# usb-led.net
KiCad netlist of a schematic drawn in EAGLE
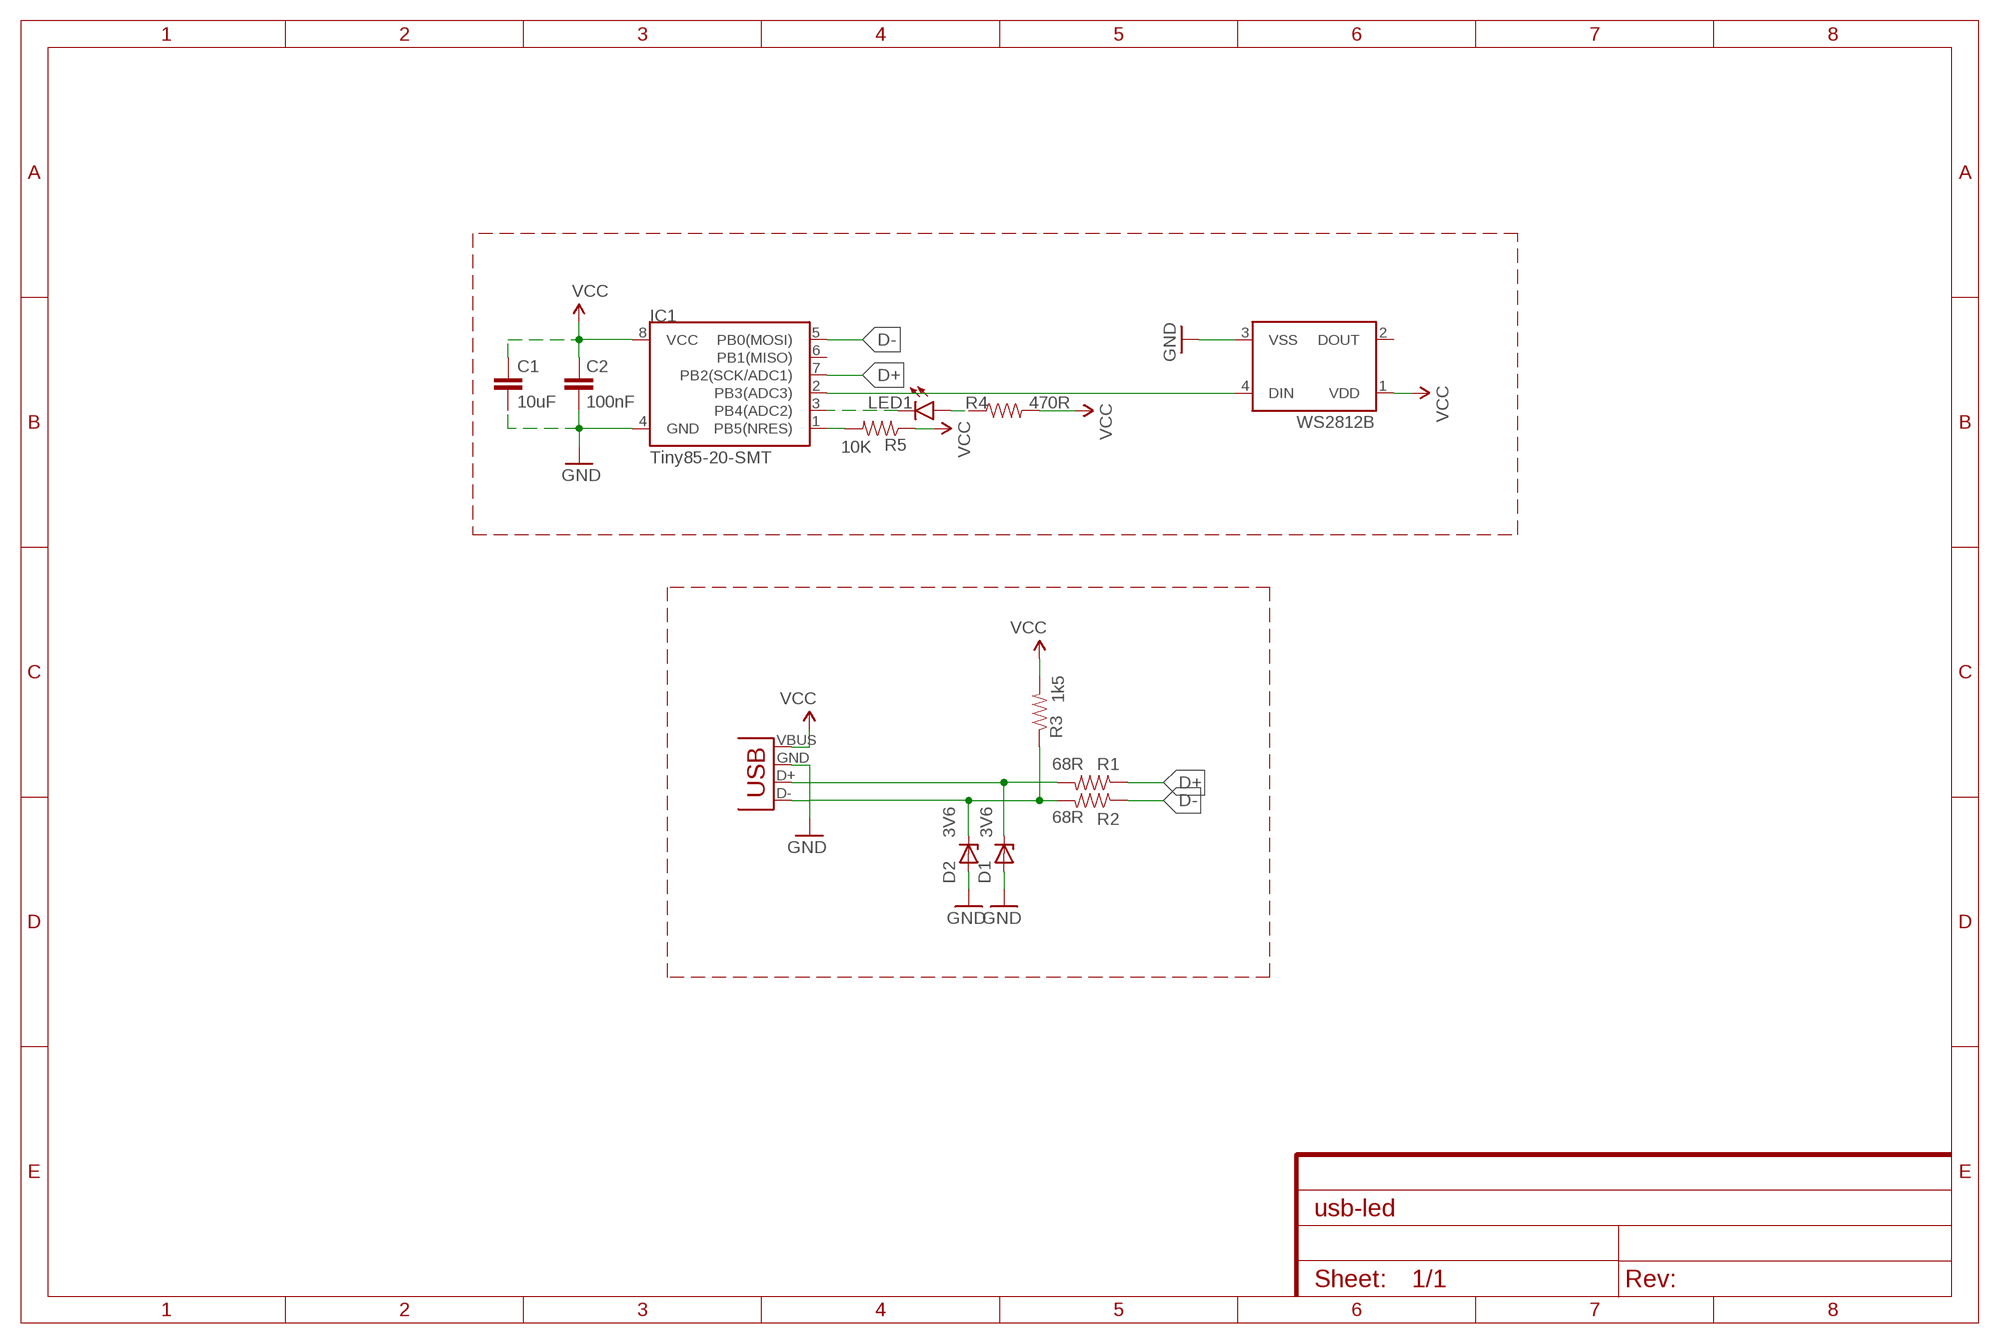
[diagram p0: schematic, sheet 1]

(export (version "E")
  (design (tool "Eeschema 10.0.6"))
  (components
    (comp (ref "C1")
      (value "10uF")
      (footprint "eagle-import:C0805")
      (libsource (lib "eagle-import") (part "C-EUC0805"))
    )
    (comp (ref "C2")
      (value "100nF")
      (footprint "eagle-import:0805")
      (libsource (lib "eagle-import") (part "CAP0805"))
    )
    (comp (ref "D1")
      (value "3V6")
      (footprint "eagle-import:ZD0603")
      (libsource (lib "eagle-import") (part "ZD0603"))
    )
    (comp (ref "D2")
      (value "3V6")
      (footprint "eagle-import:ZD0603")
      (libsource (lib "eagle-import") (part "ZD0603"))
    )
    (comp (ref "IC1")
      (value "Tiny85-20-SMT")
      (footprint "eagle-import:SO08-EIAJ")
      (libsource (lib "eagle-import") (part "ATTINY45TINY85-20-SMT"))
    )
    (comp (ref "LED1")
      (value "LED0603")
      (footprint "eagle-import:LED-0603")
      (libsource (lib "eagle-import") (part "LED0603"))
    )
    (comp (ref "R1")
      (value "68R")
      (footprint "eagle-import:0603-RES")
      (libsource (lib "eagle-import") (part "RESISTOR0603"))
    )
    (comp (ref "R2")
      (value "68R")
      (footprint "eagle-import:0603-RES")
      (libsource (lib "eagle-import") (part "RESISTOR0603"))
    )
    (comp (ref "R3")
      (value "1k5")
      (footprint "eagle-import:0603-RES")
      (libsource (lib "eagle-import") (part "RESISTOR0603"))
    )
    (comp (ref "R4")
      (value "470R")
      (footprint "eagle-import:0603-RES")
      (libsource (lib "eagle-import") (part "RESISTOR0603"))
    )
    (comp (ref "R5")
      (value "10K")
      (footprint "eagle-import:0603-RES")
      (libsource (lib "eagle-import") (part "RESISTOR0603-RES"))
    )
    (comp (ref "USB")
      (value "USB-A-H")
      (footprint "eagle-import:USB-A-H")
      (libsource (lib "eagle-import") (part "USB-A-H"))
    )
    (comp (ref "WS2812B")
      (value "WS2812B")
      (footprint "eagle-import:WS2812B")
      (libsource (lib "eagle-import") (part "WS2812B"))
    )
  )
  (nets
    (net (code "1") (name "/EXT_D-") (class "Default")
      (node (ref "D2") (pin "K") (pinfunction "C_K") (pintype "passive"))
      (node (ref "R2") (pin "2") (pinfunction "2_2") (pintype "passive"))
      (node (ref "R3") (pin "1") (pinfunction "1_1") (pintype "passive"))
      (node (ref "USB") (pin "D-") (pinfunction "D+_D-") (pintype "bidirectional"))
    )
    (net (code "2") (name "D+") (class "Default")
      (node (ref "IC1") (pin "7") (pinfunction "PB2(SCK/ADC1)_7") (pintype "bidirectional"))
      (node (ref "R1") (pin "1") (pinfunction "1_1") (pintype "passive"))
    )
    (net (code "3") (name "D-") (class "Default")
      (node (ref "IC1") (pin "5") (pinfunction "PB0(MOSI)_5") (pintype "bidirectional"))
      (node (ref "R2") (pin "1") (pinfunction "1_1") (pintype "passive"))
    )
    (net (code "4") (name "GND") (class "Default")
      (node (ref "C1") (pin "2") (pinfunction "2_2") (pintype "passive"))
      (node (ref "C2") (pin "2") (pinfunction "2_2") (pintype "passive"))
      (node (ref "D1") (pin "A") (pinfunction "A_A") (pintype "passive"))
      (node (ref "D2") (pin "A") (pinfunction "A_A") (pintype "passive"))
      (node (ref "IC1") (pin "4") (pinfunction "GND_4") (pintype "bidirectional"))
      (node (ref "USB") (pin "GND") (pinfunction "VBUS_GND") (pintype "bidirectional"))
      (node (ref "WS2812B") (pin "3") (pinfunction "VSS_3") (pintype "power_in"))
    )
    (net (code "5") (name "Net-(D1-C)") (class "Default")
      (node (ref "D1") (pin "K") (pinfunction "C_K") (pintype "passive"))
      (node (ref "R1") (pin "2") (pinfunction "2_2") (pintype "passive"))
      (node (ref "USB") (pin "D+") (pinfunction "D-_D+") (pintype "bidirectional"))
    )
    (net (code "6") (name "Net-(IC1-PB3(ADC3))") (class "Default")
      (node (ref "IC1") (pin "2") (pinfunction "PB3(ADC3)_2") (pintype "bidirectional"))
      (node (ref "WS2812B") (pin "4") (pinfunction "DIN_4") (pintype "input"))
    )
    (net (code "7") (name "Net-(IC1-PB4(ADC2))") (class "Default")
      (node (ref "IC1") (pin "3") (pinfunction "PB4(ADC2)_3") (pintype "bidirectional"))
      (node (ref "LED1") (pin "C") (pinfunction "C_C") (pintype "passive"))
    )
    (net (code "8") (name "Net-(IC1-PB5(NRES))") (class "Default")
      (node (ref "IC1") (pin "1") (pinfunction "PB5(NRES)_1") (pintype "bidirectional"))
      (node (ref "R5") (pin "2") (pinfunction "2_2") (pintype "passive"))
    )
    (net (code "9") (name "Net-(LED1-PadA)") (class "Default")
      (node (ref "LED1") (pin "A") (pinfunction "A_A") (pintype "passive"))
      (node (ref "R4") (pin "1") (pinfunction "1_1") (pintype "passive"))
    )
    (net (code "10") (name "VCC") (class "Default")
      (node (ref "C1") (pin "1") (pinfunction "1_1") (pintype "passive"))
      (node (ref "C2") (pin "1") (pinfunction "1_1") (pintype "passive"))
      (node (ref "IC1") (pin "8") (pinfunction "VCC_8") (pintype "bidirectional"))
      (node (ref "R3") (pin "2") (pinfunction "2_2") (pintype "passive"))
      (node (ref "R4") (pin "2") (pinfunction "2_2") (pintype "passive"))
      (node (ref "R5") (pin "1") (pinfunction "1_1") (pintype "passive"))
      (node (ref "USB") (pin "VBUS") (pinfunction "GND_VBUS") (pintype "bidirectional"))
      (node (ref "WS2812B") (pin "1") (pinfunction "VDD_1") (pintype "power_in"))
    )
    (net (code "11") (name "unconnected-(IC1-PB1(MISO)-Pad6)") (class "Default")
      (node (ref "IC1") (pin "6") (pinfunction "PB1(MISO)_6") (pintype "bidirectional"))
    )
    (net (code "12") (name "unconnected-(WS2812B-DOUT-Pad2)") (class "Default")
      (node (ref "WS2812B") (pin "2") (pinfunction "DOUT_2") (pintype "output"))
    )
  )
)
